# picodev.net
KiCad netlist of a schematic drawn in EAGLE
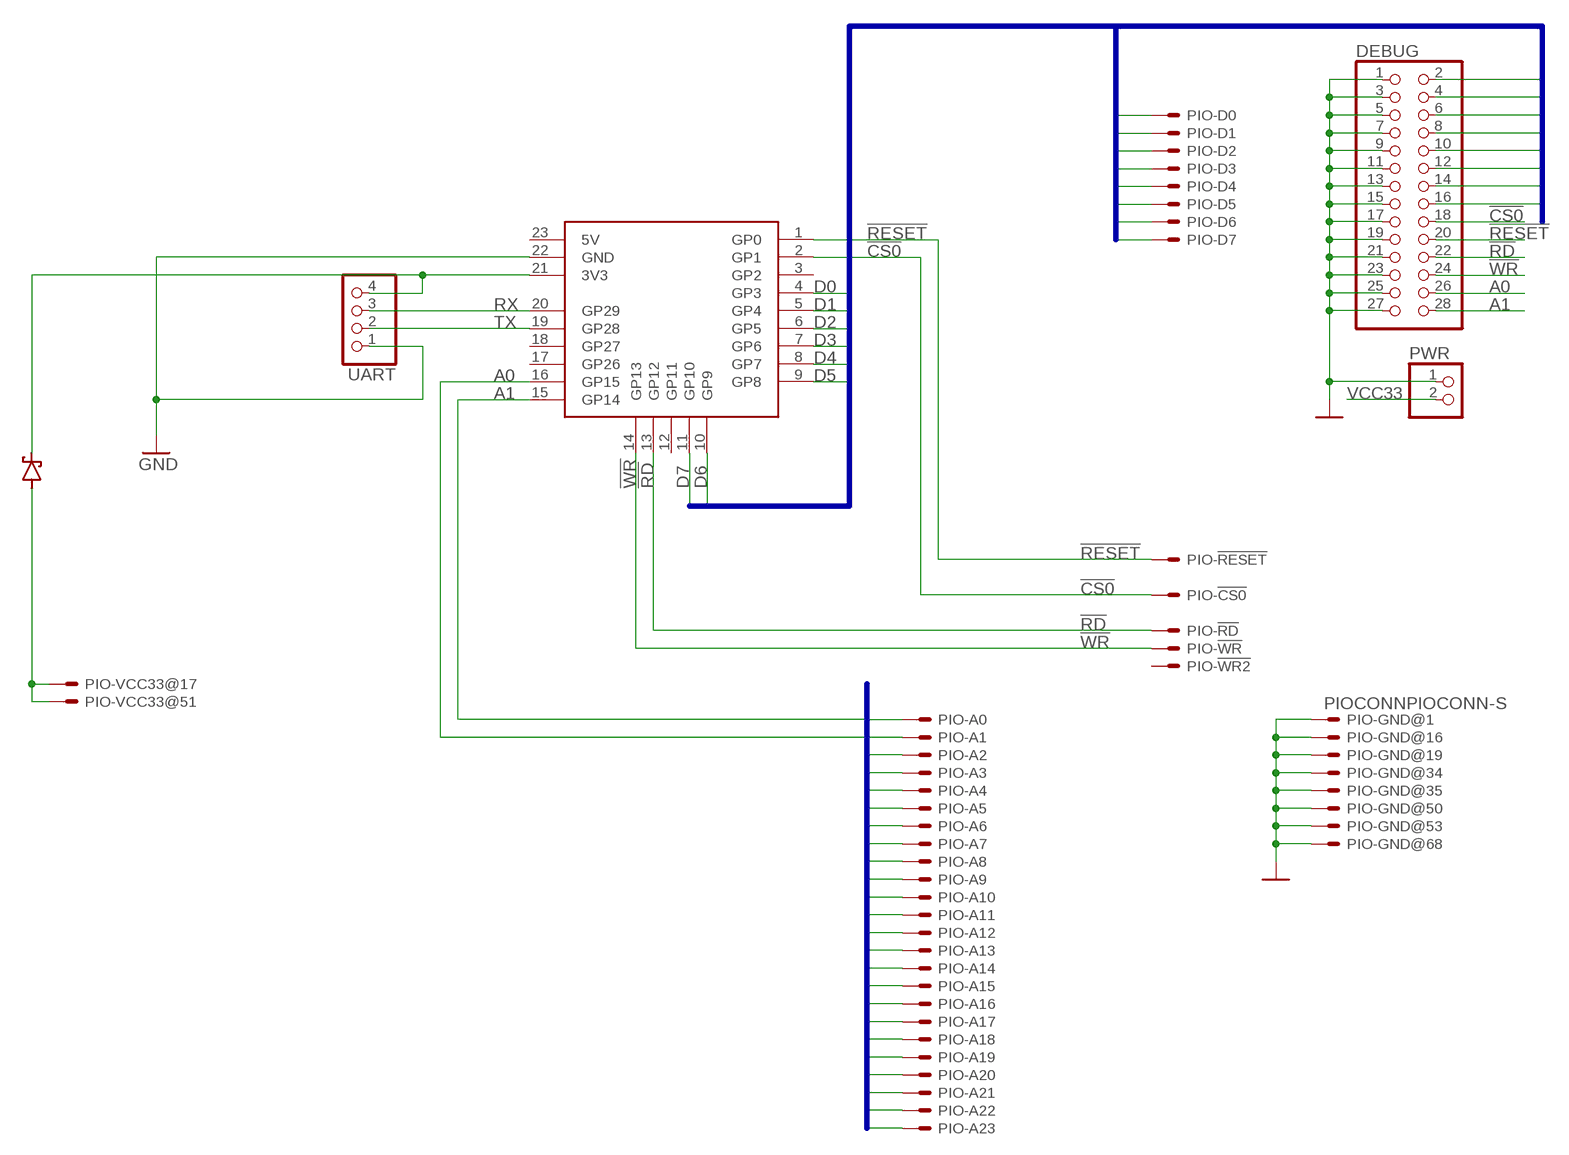
[diagram p0: schematic, sheet 1, part 1 of 2]
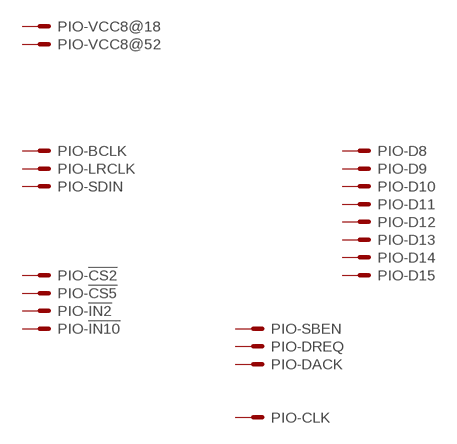
[diagram p1: schematic, sheet 1, part 2 of 2]

(export (version "E")
  (design (tool "Eeschema 10.0.6"))
  (components
    (comp (ref "D")
      (value "SCHOTTKYSMA")
      (footprint "eagle-import:SMADIODE")
      (libsource (lib "eagle-import") (part "SCHOTTKYSMA"))
    )
    (comp (ref "DEBUG")
      (value "PINHD-2X14")
      (footprint "eagle-import:2X14")
      (libsource (lib "eagle-import") (part "PINHD-2X14"))
    )
    (comp (ref "PIO")
      (value "PIOCONNPIOCONN-S")
      (footprint "eagle-import:PIOCONN")
      (libsource (lib "eagle-import") (part "PIOCONNPIOCONN-S"))
    )
    (comp (ref "PWR")
      (value "PINHD-1X2")
      (footprint "eagle-import:1X02")
      (libsource (lib "eagle-import") (part "PINHD-1X2"))
    )
    (comp (ref "U$1")
      (value "PICO-ZERO")
      (footprint "eagle-import:PICO-ZERO")
      (libsource (lib "eagle-import") (part "PICO-ZERO"))
    )
    (comp (ref "UART")
      (value "PINHD-1X4")
      (footprint "eagle-import:1X04")
      (libsource (lib "eagle-import") (part "PINHD-1X4"))
    )
  )
  (nets
    (net (code "1") (name "/A0") (class "Default")
      (node (ref "DEBUG") (pin "26") (pinfunction "26_26") (pintype "passive"))
      (node (ref "PIO") (pin "14") (pinfunction "S_14") (pintype "passive"))
      (node (ref "U$1") (pin "16") (pinfunction "GP15_16") (pintype "bidirectional"))
    )
    (net (code "2") (name "/A1") (class "Default")
      (node (ref "DEBUG") (pin "28") (pinfunction "28_28") (pintype "passive"))
      (node (ref "PIO") (pin "48") (pinfunction "S_48") (pintype "passive"))
      (node (ref "U$1") (pin "15") (pinfunction "GP14_15") (pintype "bidirectional"))
    )
    (net (code "3") (name "/D0") (class "Default")
      (node (ref "DEBUG") (pin "16") (pinfunction "16_16") (pintype "passive"))
      (node (ref "PIO") (pin "6") (pinfunction "S_6") (pintype "passive"))
      (node (ref "U$1") (pin "4") (pinfunction "GP3_4") (pintype "bidirectional"))
    )
    (net (code "4") (name "/D1") (class "Default")
      (node (ref "DEBUG") (pin "14") (pinfunction "14_14") (pintype "passive"))
      (node (ref "PIO") (pin "40") (pinfunction "S_40") (pintype "passive"))
      (node (ref "U$1") (pin "5") (pinfunction "GP4_5") (pintype "bidirectional"))
    )
    (net (code "5") (name "/D2") (class "Default")
      (node (ref "DEBUG") (pin "12") (pinfunction "12_12") (pintype "passive"))
      (node (ref "PIO") (pin "7") (pinfunction "S_7") (pintype "passive"))
      (node (ref "U$1") (pin "6") (pinfunction "GP5_6") (pintype "bidirectional"))
    )
    (net (code "6") (name "/D3") (class "Default")
      (node (ref "DEBUG") (pin "10") (pinfunction "10_10") (pintype "passive"))
      (node (ref "PIO") (pin "41") (pinfunction "S_41") (pintype "passive"))
      (node (ref "U$1") (pin "7") (pinfunction "GP6_7") (pintype "bidirectional"))
    )
    (net (code "7") (name "/D4") (class "Default")
      (node (ref "DEBUG") (pin "8") (pinfunction "8_8") (pintype "passive"))
      (node (ref "PIO") (pin "8") (pinfunction "S_8") (pintype "passive"))
      (node (ref "U$1") (pin "8") (pinfunction "GP7_8") (pintype "bidirectional"))
    )
    (net (code "8") (name "/D5") (class "Default")
      (node (ref "DEBUG") (pin "6") (pinfunction "6_6") (pintype "passive"))
      (node (ref "PIO") (pin "42") (pinfunction "S_42") (pintype "passive"))
      (node (ref "U$1") (pin "9") (pinfunction "GP8_9") (pintype "bidirectional"))
    )
    (net (code "9") (name "/D6") (class "Default")
      (node (ref "DEBUG") (pin "4") (pinfunction "4_4") (pintype "passive"))
      (node (ref "PIO") (pin "9") (pinfunction "S_9") (pintype "passive"))
      (node (ref "U$1") (pin "10") (pinfunction "GP9_10") (pintype "bidirectional"))
    )
    (net (code "10") (name "/D7") (class "Default")
      (node (ref "DEBUG") (pin "2") (pinfunction "2_2") (pintype "passive"))
      (node (ref "PIO") (pin "43") (pinfunction "S_43") (pintype "passive"))
      (node (ref "U$1") (pin "11") (pinfunction "GP10_11") (pintype "bidirectional"))
    )
    (net (code "11") (name "/RX") (class "Default")
      (node (ref "U$1") (pin "20") (pinfunction "GP29_20") (pintype "bidirectional"))
      (node (ref "UART") (pin "3") (pinfunction "3_3") (pintype "passive"))
    )
    (net (code "12") (name "/TX") (class "Default")
      (node (ref "U$1") (pin "19") (pinfunction "GP28_19") (pintype "bidirectional"))
      (node (ref "UART") (pin "2") (pinfunction "2_2") (pintype "passive"))
    )
    (net (code "13") (name "/VCC33") (class "Default")
      (node (ref "D") (pin "C") (pinfunction "C_C") (pintype "passive"))
      (node (ref "PWR") (pin "2") (pinfunction "2_2") (pintype "passive"))
      (node (ref "U$1") (pin "21") (pinfunction "3V3_21") (pintype "bidirectional"))
      (node (ref "UART") (pin "4") (pinfunction "4_4") (pintype "passive"))
    )
    (net (code "14") (name "/~{CS0}") (class "Default")
      (node (ref "DEBUG") (pin "18") (pinfunction "18_18") (pintype "passive"))
      (node (ref "PIO") (pin "4") (pinfunction "S_4") (pintype "passive"))
      (node (ref "U$1") (pin "2") (pinfunction "GP1_2") (pintype "bidirectional"))
    )
    (net (code "15") (name "/~{RD}") (class "Default")
      (node (ref "DEBUG") (pin "22") (pinfunction "22_22") (pintype "passive"))
      (node (ref "PIO") (pin "30") (pinfunction "S_30") (pintype "passive"))
      (node (ref "U$1") (pin "13") (pinfunction "GP12_13") (pintype "bidirectional"))
    )
    (net (code "16") (name "/~{RESET}") (class "Default")
      (node (ref "DEBUG") (pin "20") (pinfunction "20_20") (pintype "passive"))
      (node (ref "PIO") (pin "2") (pinfunction "S_2") (pintype "passive"))
      (node (ref "U$1") (pin "1") (pinfunction "GP0_1") (pintype "bidirectional"))
    )
    (net (code "17") (name "/~{WR}") (class "Default")
      (node (ref "DEBUG") (pin "24") (pinfunction "24_24") (pintype "passive"))
      (node (ref "PIO") (pin "64") (pinfunction "S_64") (pintype "passive"))
      (node (ref "U$1") (pin "14") (pinfunction "GP13_14") (pintype "bidirectional"))
    )
    (net (code "18") (name "GND") (class "Default")
      (node (ref "DEBUG") (pin "1") (pinfunction "1_1") (pintype "passive"))
      (node (ref "DEBUG") (pin "11") (pinfunction "11_11") (pintype "passive"))
      (node (ref "DEBUG") (pin "13") (pinfunction "13_13") (pintype "passive"))
      (node (ref "DEBUG") (pin "15") (pinfunction "15_15") (pintype "passive"))
      (node (ref "DEBUG") (pin "17") (pinfunction "17_17") (pintype "passive"))
      (node (ref "DEBUG") (pin "19") (pinfunction "19_19") (pintype "passive"))
      (node (ref "DEBUG") (pin "21") (pinfunction "21_21") (pintype "passive"))
      (node (ref "DEBUG") (pin "23") (pinfunction "23_23") (pintype "passive"))
      (node (ref "DEBUG") (pin "25") (pinfunction "25_25") (pintype "passive"))
      (node (ref "DEBUG") (pin "27") (pinfunction "27_27") (pintype "passive"))
      (node (ref "DEBUG") (pin "3") (pinfunction "3_3") (pintype "passive"))
      (node (ref "DEBUG") (pin "5") (pinfunction "5_5") (pintype "passive"))
      (node (ref "DEBUG") (pin "7") (pinfunction "7_7") (pintype "passive"))
      (node (ref "DEBUG") (pin "9") (pinfunction "9_9") (pintype "passive"))
      (node (ref "PIO") (pin "1") (pinfunction "S_1") (pintype "passive"))
      (node (ref "PIO") (pin "16") (pinfunction "S_16") (pintype "passive"))
      (node (ref "PIO") (pin "19") (pinfunction "S_19") (pintype "passive"))
      (node (ref "PIO") (pin "34") (pinfunction "S_34") (pintype "passive"))
      (node (ref "PIO") (pin "35") (pinfunction "S_35") (pintype "passive"))
      (node (ref "PIO") (pin "50") (pinfunction "S_50") (pintype "passive"))
      (node (ref "PIO") (pin "53") (pinfunction "S_53") (pintype "passive"))
      (node (ref "PIO") (pin "68") (pinfunction "S_68") (pintype "passive"))
      (node (ref "PWR") (pin "1") (pinfunction "1_1") (pintype "passive"))
      (node (ref "U$1") (pin "22") (pinfunction "GND_22") (pintype "bidirectional"))
      (node (ref "UART") (pin "1") (pinfunction "1_1") (pintype "passive"))
    )
    (net (code "19") (name "Net-(PIOBM-S)") (class "Default")
      (node (ref "D") (pin "A") (pinfunction "A_A") (pintype "passive"))
      (node (ref "PIO") (pin "17") (pinfunction "S_17") (pintype "passive"))
      (node (ref "PIO") (pin "51") (pinfunction "S_51") (pintype "passive"))
    )
    (net (code "20") (name "unconnected-(PIOAA-S-Pad49)") (class "Default")
      (node (ref "PIO") (pin "49") (pinfunction "S_49") (pintype "passive"))
    )
    (net (code "21") (name "unconnected-(PIOAB-S-Pad20)") (class "Default")
      (node (ref "PIO") (pin "20") (pinfunction "S_20") (pintype "passive"))
    )
    (net (code "22") (name "unconnected-(PIOAC-S-Pad54)") (class "Default")
      (node (ref "PIO") (pin "54") (pinfunction "S_54") (pintype "passive"))
    )
    (net (code "23") (name "unconnected-(PIOAD-S-Pad21)") (class "Default")
      (node (ref "PIO") (pin "21") (pinfunction "S_21") (pintype "passive"))
    )
    (net (code "24") (name "unconnected-(PIOAE-S-Pad55)") (class "Default")
      (node (ref "PIO") (pin "55") (pinfunction "S_55") (pintype "passive"))
    )
    (net (code "25") (name "unconnected-(PIOAF-S-Pad22)") (class "Default")
      (node (ref "PIO") (pin "22") (pinfunction "S_22") (pintype "passive"))
    )
    (net (code "26") (name "unconnected-(PIOAG-S-Pad56)") (class "Default")
      (node (ref "PIO") (pin "56") (pinfunction "S_56") (pintype "passive"))
    )
    (net (code "27") (name "unconnected-(PIOAH-S-Pad33)") (class "Default")
      (node (ref "PIO") (pin "33") (pinfunction "S_33") (pintype "passive"))
    )
    (net (code "28") (name "unconnected-(PIOAI-S-Pad32)") (class "Default")
      (node (ref "PIO") (pin "32") (pinfunction "S_32") (pintype "passive"))
    )
    (net (code "29") (name "unconnected-(PIOAL-S-Pad11)") (class "Default")
      (node (ref "PIO") (pin "11") (pinfunction "S_11") (pintype "passive"))
    )
    (net (code "30") (name "unconnected-(PIOAM-S-Pad45)") (class "Default")
      (node (ref "PIO") (pin "45") (pinfunction "S_45") (pintype "passive"))
    )
    (net (code "31") (name "unconnected-(PIOAN-S-Pad12)") (class "Default")
      (node (ref "PIO") (pin "12") (pinfunction "S_12") (pintype "passive"))
    )
    (net (code "32") (name "unconnected-(PIOAO-S-Pad46)") (class "Default")
      (node (ref "PIO") (pin "46") (pinfunction "S_46") (pintype "passive"))
    )
    (net (code "33") (name "unconnected-(PIOAP-S-Pad13)") (class "Default")
      (node (ref "PIO") (pin "13") (pinfunction "S_13") (pintype "passive"))
    )
    (net (code "34") (name "unconnected-(PIOAQ-S-Pad47)") (class "Default")
      (node (ref "PIO") (pin "47") (pinfunction "S_47") (pintype "passive"))
    )
    (net (code "35") (name "unconnected-(PIOAX-S-Pad10)") (class "Default")
      (node (ref "PIO") (pin "10") (pinfunction "S_10") (pintype "passive"))
    )
    (net (code "36") (name "unconnected-(PIOAY-S-Pad44)") (class "Default")
      (node (ref "PIO") (pin "44") (pinfunction "S_44") (pintype "passive"))
    )
    (net (code "37") (name "unconnected-(PIOAZ-S-Pad36)") (class "Default")
      (node (ref "PIO") (pin "36") (pinfunction "S_36") (pintype "passive"))
    )
    (net (code "38") (name "unconnected-(PIOB-S-Pad39)") (class "Default")
      (node (ref "PIO") (pin "39") (pinfunction "S_39") (pintype "passive"))
    )
    (net (code "39") (name "unconnected-(PIOBA-S-Pad3)") (class "Default")
      (node (ref "PIO") (pin "3") (pinfunction "S_3") (pintype "passive"))
    )
    (net (code "40") (name "unconnected-(PIOBJ-S-Pad66)") (class "Default")
      (node (ref "PIO") (pin "66") (pinfunction "S_66") (pintype "passive"))
    )
    (net (code "41") (name "unconnected-(PIOBK-S-Pad5)") (class "Default")
      (node (ref "PIO") (pin "5") (pinfunction "S_5") (pintype "passive"))
    )
    (net (code "42") (name "unconnected-(PIOBL-S-Pad67)") (class "Default")
      (node (ref "PIO") (pin "67") (pinfunction "S_67") (pintype "passive"))
    )
    (net (code "43") (name "unconnected-(PIOBO-S-Pad18)") (class "Default")
      (node (ref "PIO") (pin "18") (pinfunction "S_18") (pintype "passive"))
    )
    (net (code "44") (name "unconnected-(PIOBP-S-Pad52)") (class "Default")
      (node (ref "PIO") (pin "52") (pinfunction "S_52") (pintype "passive"))
    )
    (net (code "45") (name "unconnected-(PIOC-S-Pad65)") (class "Default")
      (node (ref "PIO") (pin "65") (pinfunction "S_65") (pintype "passive"))
    )
    (net (code "46") (name "unconnected-(PIOD-S-Pad37)") (class "Default")
      (node (ref "PIO") (pin "37") (pinfunction "S_37") (pintype "passive"))
    )
    (net (code "47") (name "unconnected-(PIOE-S-Pad31)") (class "Default")
      (node (ref "PIO") (pin "31") (pinfunction "S_31") (pintype "passive"))
    )
    (net (code "48") (name "unconnected-(PIOI-S-Pad38)") (class "Default")
      (node (ref "PIO") (pin "38") (pinfunction "S_38") (pintype "passive"))
    )
    (net (code "49") (name "unconnected-(PIOL-S-Pad23)") (class "Default")
      (node (ref "PIO") (pin "23") (pinfunction "S_23") (pintype "passive"))
    )
    (net (code "50") (name "unconnected-(PIOM-S-Pad57)") (class "Default")
      (node (ref "PIO") (pin "57") (pinfunction "S_57") (pintype "passive"))
    )
    (net (code "51") (name "unconnected-(PION-S-Pad24)") (class "Default")
      (node (ref "PIO") (pin "24") (pinfunction "S_24") (pintype "passive"))
    )
    (net (code "52") (name "unconnected-(PIOO-S-Pad58)") (class "Default")
      (node (ref "PIO") (pin "58") (pinfunction "S_58") (pintype "passive"))
    )
    (net (code "53") (name "unconnected-(PIOP-S-Pad25)") (class "Default")
      (node (ref "PIO") (pin "25") (pinfunction "S_25") (pintype "passive"))
    )
    (net (code "54") (name "unconnected-(PIOQ-S-Pad59)") (class "Default")
      (node (ref "PIO") (pin "59") (pinfunction "S_59") (pintype "passive"))
    )
    (net (code "55") (name "unconnected-(PIOR-S-Pad26)") (class "Default")
      (node (ref "PIO") (pin "26") (pinfunction "S_26") (pintype "passive"))
    )
    (net (code "56") (name "unconnected-(PIOS-S-Pad60)") (class "Default")
      (node (ref "PIO") (pin "60") (pinfunction "S_60") (pintype "passive"))
    )
    (net (code "57") (name "unconnected-(PIOT-S-Pad27)") (class "Default")
      (node (ref "PIO") (pin "27") (pinfunction "S_27") (pintype "passive"))
    )
    (net (code "58") (name "unconnected-(PIOU-S-Pad61)") (class "Default")
      (node (ref "PIO") (pin "61") (pinfunction "S_61") (pintype "passive"))
    )
    (net (code "59") (name "unconnected-(PIOV-S-Pad15)") (class "Default")
      (node (ref "PIO") (pin "15") (pinfunction "S_15") (pintype "passive"))
    )
    (net (code "60") (name "unconnected-(PIOW-S-Pad28)") (class "Default")
      (node (ref "PIO") (pin "28") (pinfunction "S_28") (pintype "passive"))
    )
    (net (code "61") (name "unconnected-(PIOX-S-Pad62)") (class "Default")
      (node (ref "PIO") (pin "62") (pinfunction "S_62") (pintype "passive"))
    )
    (net (code "62") (name "unconnected-(PIOY-S-Pad29)") (class "Default")
      (node (ref "PIO") (pin "29") (pinfunction "S_29") (pintype "passive"))
    )
    (net (code "63") (name "unconnected-(PIOZ-S-Pad63)") (class "Default")
      (node (ref "PIO") (pin "63") (pinfunction "S_63") (pintype "passive"))
    )
    (net (code "64") (name "unconnected-(U$1-5V-Pad23)") (class "Default")
      (node (ref "U$1") (pin "23") (pinfunction "5V_23") (pintype "bidirectional"))
    )
    (net (code "65") (name "unconnected-(U$1-GP2-Pad3)") (class "Default")
      (node (ref "U$1") (pin "3") (pinfunction "GP2_3") (pintype "bidirectional"))
    )
    (net (code "66") (name "unconnected-(U$1-GP11-Pad12)") (class "Default")
      (node (ref "U$1") (pin "12") (pinfunction "GP11_12") (pintype "bidirectional"))
    )
    (net (code "67") (name "unconnected-(U$1-GP26-Pad17)") (class "Default")
      (node (ref "U$1") (pin "17") (pinfunction "GP26_17") (pintype "bidirectional"))
    )
    (net (code "68") (name "unconnected-(U$1-GP27-Pad18)") (class "Default")
      (node (ref "U$1") (pin "18") (pinfunction "GP27_18") (pintype "bidirectional"))
    )
  )
)
